# synth.net
KiCad netlist of a schematic drawn in Altium Designer
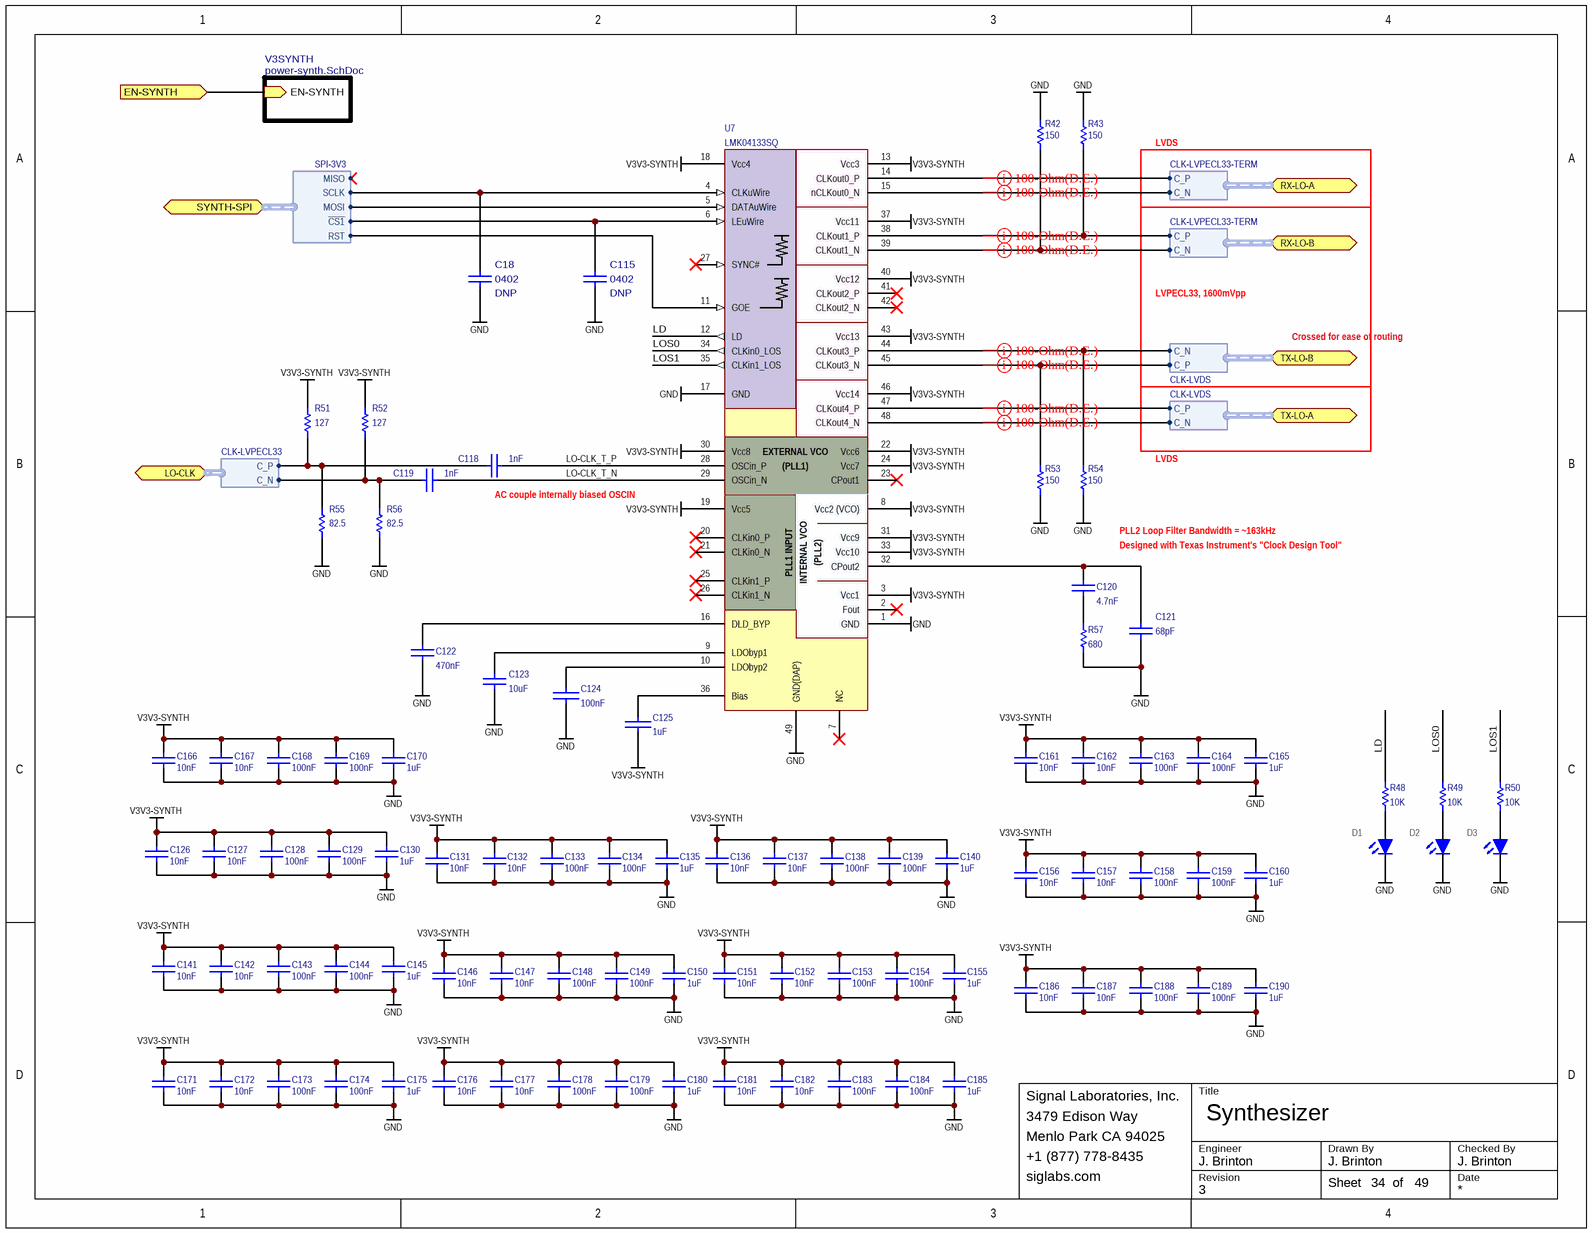
[diagram p0: synth.SchDoc]

(export (version "E")
  (design (tool "Eeschema 10.0.6"))
  (components
    (comp (ref "C18")
      (value "VJ0402A101KXA")
      (footprint "CAPC100X50X55L25N")
      (description "Ceramic Capacitor 100pF ±10% 50V C0G 0402")
      (fields
        (field (name "MANUFACTURER") "Vishay")
        (field (name "TOLERANCE") "±10%")
        (field (name "PACKAGE") "0402")
        (field (name "DO NOT PLACE") "DNP")
      )
      (libsource (lib "capacitors") (part "CAP"))
    )
    (comp (ref "C115")
      (value "VJ0402A101KXA")
      (footprint "CAPC100X50X55L25N")
      (description "Ceramic Capacitor 100pF ±10% 50V C0G 0402")
      (fields
        (field (name "MANUFACTURER") "Vishay")
        (field (name "TOLERANCE") "±10%")
        (field (name "PACKAGE") "0402")
        (field (name "DO NOT PLACE") "DNP")
      )
      (libsource (lib "capacitors") (part "CAP"))
    )
    (comp (ref "C118")
      (value "1nF")
      (footprint "CAPC100X50X55L25N")
      (description "Ceramic Capacitor 1nF ±5% 50V NP0 0402")
      (fields (field (name "VOLTAGE") "50V") (field (name "MANUFACTURER") "TDK"))
      (libsource (lib "Graviton") (part "CAP 0402"))
    )
    (comp (ref "C119")
      (value "1nF")
      (footprint "CAPC100X50X55L25N")
      (description "Ceramic Capacitor 1nF ±5% 50V NP0 0402")
      (fields (field (name "VOLTAGE") "50V") (field (name "MANUFACTURER") "TDK"))
      (libsource (lib "Graviton") (part "CAP 0402"))
    )
    (comp (ref "C120")
      (value "4.7nF")
      (footprint "CAPC100X50X55L25N")
      (description "Ceramic Capacitor 4.7nF ±5% 50V X7R 0402")
      (fields (field (name "VOLTAGE") "50V") (field (name "MANUFACTURER") "Murata"))
      (libsource (lib "Graviton") (part "CAP 0402"))
    )
    (comp (ref "C121")
      (value "68pF")
      (footprint "CAPC100X50X55L25N")
      (description "Ceramic Capacitor 68pF ±2% 50V NP0 0402")
      (fields (field (name "VOLTAGE") "50V") (field (name "MANUFACTURER") "Murata"))
      (libsource (lib "Graviton") (part "CAP 0402"))
    )
    (comp (ref "C122")
      (value "470nF")
      (footprint "CAPC200X125X145L45N")
      (description "Ceramic Capacitor 470nF ±10% 50V X7R 0805")
      (fields (field (name "VOLTAGE") "50V") (field (name "MANUFACTURER") "Kemet"))
      (libsource (lib "Graviton") (part "CAP 0402"))
    )
    (comp (ref "C123")
      (value "10uF")
      (footprint "CAPC160X80X90L20N")
      (description "Ceramic Capacitor 10uF ±20% 25V X5R 0603")
      (fields (field (name "VOLTAGE") "25V") (field (name "MANUFACTURER") "Murata"))
      (libsource (lib "Graviton") (part "CAP 0402"))
    )
    (comp (ref "C124")
      (value "100nF")
      (footprint "CAPC100X50X55L25N")
      (description "Ceramic Capacitor 100nF ±10% 16V X7R 0402")
      (fields (field (name "MANUFACTURER") "Murata") (field (name "VOLTAGE") "16V"))
      (libsource (lib "*") (part "CAP"))
    )
    (comp (ref "C125")
      (value "1uF")
      (footprint "CAPC100X50X55L25N")
      (description "Ceramic Capacitor 1uF ±10% 10V X5R 0402")
      (fields (field (name "MANUFACTURER") "Murata") (field (name "TOLERANCE") "±10%"))
      (libsource (lib "*") (part "CAP"))
    )
    (comp (ref "C126")
      (value "10nF")
      (footprint "CAPC100X50X55L25N")
      (description "Ceramic Capacitor 10nF ±10% 50V X7R 0402")
      (fields (field (name "VOLTAGE") "50V") (field (name "MANUFACTURER") "Murata"))
      (libsource (lib "Graviton") (part "CAP 0402"))
    )
    (comp (ref "C127")
      (value "10nF")
      (footprint "CAPC100X50X55L25N")
      (description "Ceramic Capacitor 10nF ±10% 50V X7R 0402")
      (fields (field (name "VOLTAGE") "50V") (field (name "MANUFACTURER") "Murata"))
      (libsource (lib "Graviton") (part "CAP 0402"))
    )
    (comp (ref "C128")
      (value "100nF")
      (footprint "CAPC100X50X55L25N")
      (description "Ceramic Capacitor 100nF ±10% 16V X7R 0402")
      (fields (field (name "VOLTAGE") "16V") (field (name "MANUFACTURER") "Murata"))
      (libsource (lib "Graviton") (part "CAP 0402"))
    )
    (comp (ref "C129")
      (value "100nF")
      (footprint "CAPC100X50X55L25N")
      (description "Ceramic Capacitor 100nF ±10% 16V X7R 0402")
      (fields (field (name "VOLTAGE") "16V") (field (name "MANUFACTURER") "Murata"))
      (libsource (lib "Graviton") (part "CAP 0402"))
    )
    (comp (ref "C130")
      (value "1uF")
      (footprint "CAPC100X50X55L25N")
      (description "Ceramic Capacitor 1uF ±10% 10V X5R 0402")
      (fields (field (name "VOLTAGE") "10V") (field (name "MANUFACTURER") "Murata"))
      (libsource (lib "Graviton") (part "CAP 0402"))
    )
    (comp (ref "C131")
      (value "10nF")
      (footprint "CAPC100X50X55L25N")
      (description "Ceramic Capacitor 10nF ±10% 50V X7R 0402")
      (fields (field (name "VOLTAGE") "50V") (field (name "MANUFACTURER") "Murata"))
      (libsource (lib "Graviton") (part "CAP 0402"))
    )
    (comp (ref "C132")
      (value "10nF")
      (footprint "CAPC100X50X55L25N")
      (description "Ceramic Capacitor 10nF ±10% 50V X7R 0402")
      (fields (field (name "VOLTAGE") "50V") (field (name "MANUFACTURER") "Murata"))
      (libsource (lib "Graviton") (part "CAP 0402"))
    )
    (comp (ref "C133")
      (value "100nF")
      (footprint "CAPC100X50X55L25N")
      (description "Ceramic Capacitor 100nF ±10% 16V X7R 0402")
      (fields (field (name "VOLTAGE") "16V") (field (name "MANUFACTURER") "Murata"))
      (libsource (lib "Graviton") (part "CAP 0402"))
    )
    (comp (ref "C134")
      (value "100nF")
      (footprint "CAPC100X50X55L25N")
      (description "Ceramic Capacitor 100nF ±10% 16V X7R 0402")
      (fields (field (name "VOLTAGE") "16V") (field (name "MANUFACTURER") "Murata"))
      (libsource (lib "Graviton") (part "CAP 0402"))
    )
    (comp (ref "C135")
      (value "1uF")
      (footprint "CAPC100X50X55L25N")
      (description "Ceramic Capacitor 1uF ±10% 10V X5R 0402")
      (fields (field (name "VOLTAGE") "10V") (field (name "MANUFACTURER") "Murata"))
      (libsource (lib "Graviton") (part "CAP 0402"))
    )
    (comp (ref "C136")
      (value "10nF")
      (footprint "CAPC100X50X55L25N")
      (description "Ceramic Capacitor 10nF ±10% 50V X7R 0402")
      (fields (field (name "VOLTAGE") "50V") (field (name "MANUFACTURER") "Murata"))
      (libsource (lib "Graviton") (part "CAP 0402"))
    )
    (comp (ref "C137")
      (value "10nF")
      (footprint "CAPC100X50X55L25N")
      (description "Ceramic Capacitor 10nF ±10% 50V X7R 0402")
      (fields (field (name "VOLTAGE") "50V") (field (name "MANUFACTURER") "Murata"))
      (libsource (lib "Graviton") (part "CAP 0402"))
    )
    (comp (ref "C138")
      (value "100nF")
      (footprint "CAPC100X50X55L25N")
      (description "Ceramic Capacitor 100nF ±10% 16V X7R 0402")
      (fields (field (name "VOLTAGE") "16V") (field (name "MANUFACTURER") "Murata"))
      (libsource (lib "Graviton") (part "CAP 0402"))
    )
    (comp (ref "C139")
      (value "100nF")
      (footprint "CAPC100X50X55L25N")
      (description "Ceramic Capacitor 100nF ±10% 16V X7R 0402")
      (fields (field (name "VOLTAGE") "16V") (field (name "MANUFACTURER") "Murata"))
      (libsource (lib "Graviton") (part "CAP 0402"))
    )
    (comp (ref "C140")
      (value "1uF")
      (footprint "CAPC100X50X55L25N")
      (description "Ceramic Capacitor 1uF ±10% 10V X5R 0402")
      (fields (field (name "VOLTAGE") "10V") (field (name "MANUFACTURER") "Murata"))
      (libsource (lib "Graviton") (part "CAP 0402"))
    )
    (comp (ref "C141")
      (value "10nF")
      (footprint "CAPC100X50X55L25N")
      (description "Ceramic Capacitor 10nF ±10% 50V X7R 0402")
      (fields (field (name "VOLTAGE") "50V") (field (name "MANUFACTURER") "Murata"))
      (libsource (lib "Graviton") (part "CAP 0402"))
    )
    (comp (ref "C142")
      (value "10nF")
      (footprint "CAPC100X50X55L25N")
      (description "Ceramic Capacitor 10nF ±10% 50V X7R 0402")
      (fields (field (name "VOLTAGE") "50V") (field (name "MANUFACTURER") "Murata"))
      (libsource (lib "Graviton") (part "CAP 0402"))
    )
    (comp (ref "C143")
      (value "100nF")
      (footprint "CAPC100X50X55L25N")
      (description "Ceramic Capacitor 100nF ±10% 16V X7R 0402")
      (fields (field (name "VOLTAGE") "16V") (field (name "MANUFACTURER") "Murata"))
      (libsource (lib "Graviton") (part "CAP 0402"))
    )
    (comp (ref "C144")
      (value "100nF")
      (footprint "CAPC100X50X55L25N")
      (description "Ceramic Capacitor 100nF ±10% 16V X7R 0402")
      (fields (field (name "VOLTAGE") "16V") (field (name "MANUFACTURER") "Murata"))
      (libsource (lib "Graviton") (part "CAP 0402"))
    )
    (comp (ref "C145")
      (value "1uF")
      (footprint "CAPC100X50X55L25N")
      (description "Ceramic Capacitor 1uF ±10% 10V X5R 0402")
      (fields (field (name "VOLTAGE") "10V") (field (name "MANUFACTURER") "Murata"))
      (libsource (lib "Graviton") (part "CAP 0402"))
    )
    (comp (ref "C146")
      (value "10nF")
      (footprint "CAPC100X50X55L25N")
      (description "Ceramic Capacitor 10nF ±10% 50V X7R 0402")
      (fields (field (name "VOLTAGE") "50V") (field (name "MANUFACTURER") "Murata"))
      (libsource (lib "Graviton") (part "CAP 0402"))
    )
    (comp (ref "C147")
      (value "10nF")
      (footprint "CAPC100X50X55L25N")
      (description "Ceramic Capacitor 10nF ±10% 50V X7R 0402")
      (fields (field (name "VOLTAGE") "50V") (field (name "MANUFACTURER") "Murata"))
      (libsource (lib "Graviton") (part "CAP 0402"))
    )
    (comp (ref "C148")
      (value "100nF")
      (footprint "CAPC100X50X55L25N")
      (description "Ceramic Capacitor 100nF ±10% 16V X7R 0402")
      (fields (field (name "VOLTAGE") "16V") (field (name "MANUFACTURER") "Murata"))
      (libsource (lib "Graviton") (part "CAP 0402"))
    )
    (comp (ref "C149")
      (value "100nF")
      (footprint "CAPC100X50X55L25N")
      (description "Ceramic Capacitor 100nF ±10% 16V X7R 0402")
      (fields (field (name "VOLTAGE") "16V") (field (name "MANUFACTURER") "Murata"))
      (libsource (lib "Graviton") (part "CAP 0402"))
    )
    (comp (ref "C150")
      (value "1uF")
      (footprint "CAPC100X50X55L25N")
      (description "Ceramic Capacitor 1uF ±10% 10V X5R 0402")
      (fields (field (name "VOLTAGE") "10V") (field (name "MANUFACTURER") "Murata"))
      (libsource (lib "Graviton") (part "CAP 0402"))
    )
    (comp (ref "C151")
      (value "10nF")
      (footprint "CAPC100X50X55L25N")
      (description "Ceramic Capacitor 10nF ±10% 50V X7R 0402")
      (fields (field (name "VOLTAGE") "50V") (field (name "MANUFACTURER") "Murata"))
      (libsource (lib "Graviton") (part "CAP 0402"))
    )
    (comp (ref "C152")
      (value "10nF")
      (footprint "CAPC100X50X55L25N")
      (description "Ceramic Capacitor 10nF ±10% 50V X7R 0402")
      (fields (field (name "VOLTAGE") "50V") (field (name "MANUFACTURER") "Murata"))
      (libsource (lib "Graviton") (part "CAP 0402"))
    )
    (comp (ref "C153")
      (value "100nF")
      (footprint "CAPC100X50X55L25N")
      (description "Ceramic Capacitor 100nF ±10% 16V X7R 0402")
      (fields (field (name "VOLTAGE") "16V") (field (name "MANUFACTURER") "Murata"))
      (libsource (lib "Graviton") (part "CAP 0402"))
    )
    (comp (ref "C154")
      (value "100nF")
      (footprint "CAPC100X50X55L25N")
      (description "Ceramic Capacitor 100nF ±10% 16V X7R 0402")
      (fields (field (name "VOLTAGE") "16V") (field (name "MANUFACTURER") "Murata"))
      (libsource (lib "Graviton") (part "CAP 0402"))
    )
    (comp (ref "C155")
      (value "1uF")
      (footprint "CAPC100X50X55L25N")
      (description "Ceramic Capacitor 1uF ±10% 10V X5R 0402")
      (fields (field (name "VOLTAGE") "10V") (field (name "MANUFACTURER") "Murata"))
      (libsource (lib "Graviton") (part "CAP 0402"))
    )
    (comp (ref "C156")
      (value "10nF")
      (footprint "CAPC100X50X55L25N")
      (description "Ceramic Capacitor 10nF ±10% 50V X7R 0402")
      (fields (field (name "VOLTAGE") "50V") (field (name "MANUFACTURER") "Murata"))
      (libsource (lib "Graviton") (part "CAP 0402"))
    )
    (comp (ref "C157")
      (value "10nF")
      (footprint "CAPC100X50X55L25N")
      (description "Ceramic Capacitor 10nF ±10% 50V X7R 0402")
      (fields (field (name "VOLTAGE") "50V") (field (name "MANUFACTURER") "Murata"))
      (libsource (lib "Graviton") (part "CAP 0402"))
    )
    (comp (ref "C158")
      (value "100nF")
      (footprint "CAPC100X50X55L25N")
      (description "Ceramic Capacitor 100nF ±10% 16V X7R 0402")
      (fields (field (name "VOLTAGE") "16V") (field (name "MANUFACTURER") "Murata"))
      (libsource (lib "Graviton") (part "CAP 0402"))
    )
    (comp (ref "C159")
      (value "100nF")
      (footprint "CAPC100X50X55L25N")
      (description "Ceramic Capacitor 100nF ±10% 16V X7R 0402")
      (fields (field (name "VOLTAGE") "16V") (field (name "MANUFACTURER") "Murata"))
      (libsource (lib "Graviton") (part "CAP 0402"))
    )
    (comp (ref "C160")
      (value "1uF")
      (footprint "CAPC100X50X55L25N")
      (description "Ceramic Capacitor 1uF ±10% 10V X5R 0402")
      (fields (field (name "VOLTAGE") "10V") (field (name "MANUFACTURER") "Murata"))
      (libsource (lib "Graviton") (part "CAP 0402"))
    )
    (comp (ref "C161")
      (value "10nF")
      (footprint "CAPC100X50X55L25N")
      (description "Ceramic Capacitor 10nF ±10% 50V X7R 0402")
      (fields (field (name "VOLTAGE") "50V") (field (name "MANUFACTURER") "Murata"))
      (libsource (lib "Graviton") (part "CAP 0402"))
    )
    (comp (ref "C162")
      (value "10nF")
      (footprint "CAPC100X50X55L25N")
      (description "Ceramic Capacitor 10nF ±10% 50V X7R 0402")
      (fields (field (name "VOLTAGE") "50V") (field (name "MANUFACTURER") "Murata"))
      (libsource (lib "Graviton") (part "CAP 0402"))
    )
    (comp (ref "C163")
      (value "100nF")
      (footprint "CAPC100X50X55L25N")
      (description "Ceramic Capacitor 100nF ±10% 16V X7R 0402")
      (fields (field (name "VOLTAGE") "16V") (field (name "MANUFACTURER") "Murata"))
      (libsource (lib "Graviton") (part "CAP 0402"))
    )
    (comp (ref "C164")
      (value "100nF")
      (footprint "CAPC100X50X55L25N")
      (description "Ceramic Capacitor 100nF ±10% 16V X7R 0402")
      (fields (field (name "VOLTAGE") "16V") (field (name "MANUFACTURER") "Murata"))
      (libsource (lib "Graviton") (part "CAP 0402"))
    )
    (comp (ref "C165")
      (value "1uF")
      (footprint "CAPC100X50X55L25N")
      (description "Ceramic Capacitor 1uF ±10% 10V X5R 0402")
      (fields (field (name "VOLTAGE") "10V") (field (name "MANUFACTURER") "Murata"))
      (libsource (lib "Graviton") (part "CAP 0402"))
    )
    (comp (ref "C166")
      (value "10nF")
      (footprint "CAPC100X50X55L25N")
      (description "Ceramic Capacitor 10nF ±10% 50V X7R 0402")
      (fields (field (name "VOLTAGE") "50V") (field (name "MANUFACTURER") "Murata"))
      (libsource (lib "Graviton") (part "CAP 0402"))
    )
    (comp (ref "C167")
      (value "10nF")
      (footprint "CAPC100X50X55L25N")
      (description "Ceramic Capacitor 10nF ±10% 50V X7R 0402")
      (fields (field (name "VOLTAGE") "50V") (field (name "MANUFACTURER") "Murata"))
      (libsource (lib "Graviton") (part "CAP 0402"))
    )
    (comp (ref "C168")
      (value "100nF")
      (footprint "CAPC100X50X55L25N")
      (description "Ceramic Capacitor 100nF ±10% 16V X7R 0402")
      (fields (field (name "VOLTAGE") "16V") (field (name "MANUFACTURER") "Murata"))
      (libsource (lib "Graviton") (part "CAP 0402"))
    )
    (comp (ref "C169")
      (value "100nF")
      (footprint "CAPC100X50X55L25N")
      (description "Ceramic Capacitor 100nF ±10% 16V X7R 0402")
      (fields (field (name "VOLTAGE") "16V") (field (name "MANUFACTURER") "Murata"))
      (libsource (lib "Graviton") (part "CAP 0402"))
    )
    (comp (ref "C170")
      (value "1uF")
      (footprint "CAPC100X50X55L25N")
      (description "Ceramic Capacitor 1uF ±10% 10V X5R 0402")
      (fields (field (name "VOLTAGE") "10V") (field (name "MANUFACTURER") "Murata"))
      (libsource (lib "Graviton") (part "CAP 0402"))
    )
    (comp (ref "C171")
      (value "10nF")
      (footprint "CAPC100X50X55L25N")
      (description "Ceramic Capacitor 10nF ±10% 50V X7R 0402")
      (fields (field (name "VOLTAGE") "50V") (field (name "MANUFACTURER") "Murata"))
      (libsource (lib "Graviton") (part "CAP 0402"))
    )
    (comp (ref "C172")
      (value "10nF")
      (footprint "CAPC100X50X55L25N")
      (description "Ceramic Capacitor 10nF ±10% 50V X7R 0402")
      (fields (field (name "VOLTAGE") "50V") (field (name "MANUFACTURER") "Murata"))
      (libsource (lib "Graviton") (part "CAP 0402"))
    )
    (comp (ref "C173")
      (value "100nF")
      (footprint "CAPC100X50X55L25N")
      (description "Ceramic Capacitor 100nF ±10% 16V X7R 0402")
      (fields (field (name "VOLTAGE") "16V") (field (name "MANUFACTURER") "Murata"))
      (libsource (lib "Graviton") (part "CAP 0402"))
    )
    (comp (ref "C174")
      (value "100nF")
      (footprint "CAPC100X50X55L25N")
      (description "Ceramic Capacitor 100nF ±10% 16V X7R 0402")
      (fields (field (name "VOLTAGE") "16V") (field (name "MANUFACTURER") "Murata"))
      (libsource (lib "Graviton") (part "CAP 0402"))
    )
    (comp (ref "C175")
      (value "1uF")
      (footprint "CAPC100X50X55L25N")
      (description "Ceramic Capacitor 1uF ±10% 10V X5R 0402")
      (fields (field (name "VOLTAGE") "10V") (field (name "MANUFACTURER") "Murata"))
      (libsource (lib "Graviton") (part "CAP 0402"))
    )
    (comp (ref "C176")
      (value "10nF")
      (footprint "CAPC100X50X55L25N")
      (description "Ceramic Capacitor 10nF ±10% 50V X7R 0402")
      (fields (field (name "VOLTAGE") "50V") (field (name "MANUFACTURER") "Murata"))
      (libsource (lib "Graviton") (part "CAP 0402"))
    )
    (comp (ref "C177")
      (value "10nF")
      (footprint "CAPC100X50X55L25N")
      (description "Ceramic Capacitor 10nF ±10% 50V X7R 0402")
      (fields (field (name "VOLTAGE") "50V") (field (name "MANUFACTURER") "Murata"))
      (libsource (lib "Graviton") (part "CAP 0402"))
    )
    (comp (ref "C178")
      (value "100nF")
      (footprint "CAPC100X50X55L25N")
      (description "Ceramic Capacitor 100nF ±10% 16V X7R 0402")
      (fields (field (name "VOLTAGE") "16V") (field (name "MANUFACTURER") "Murata"))
      (libsource (lib "Graviton") (part "CAP 0402"))
    )
    (comp (ref "C179")
      (value "100nF")
      (footprint "CAPC100X50X55L25N")
      (description "Ceramic Capacitor 100nF ±10% 16V X7R 0402")
      (fields (field (name "VOLTAGE") "16V") (field (name "MANUFACTURER") "Murata"))
      (libsource (lib "Graviton") (part "CAP 0402"))
    )
    (comp (ref "C180")
      (value "1uF")
      (footprint "CAPC100X50X55L25N")
      (description "Ceramic Capacitor 1uF ±10% 10V X5R 0402")
      (fields (field (name "VOLTAGE") "10V") (field (name "MANUFACTURER") "Murata"))
      (libsource (lib "Graviton") (part "CAP 0402"))
    )
    (comp (ref "C181")
      (value "10nF")
      (footprint "CAPC100X50X55L25N")
      (description "Ceramic Capacitor 10nF ±10% 50V X7R 0402")
      (fields (field (name "VOLTAGE") "50V") (field (name "MANUFACTURER") "Murata"))
      (libsource (lib "Graviton") (part "CAP 0402"))
    )
    (comp (ref "C182")
      (value "10nF")
      (footprint "CAPC100X50X55L25N")
      (description "Ceramic Capacitor 10nF ±10% 50V X7R 0402")
      (fields (field (name "VOLTAGE") "50V") (field (name "MANUFACTURER") "Murata"))
      (libsource (lib "Graviton") (part "CAP 0402"))
    )
    (comp (ref "C183")
      (value "100nF")
      (footprint "CAPC100X50X55L25N")
      (description "Ceramic Capacitor 100nF ±10% 16V X7R 0402")
      (fields (field (name "VOLTAGE") "16V") (field (name "MANUFACTURER") "Murata"))
      (libsource (lib "Graviton") (part "CAP 0402"))
    )
    (comp (ref "C184")
      (value "100nF")
      (footprint "CAPC100X50X55L25N")
      (description "Ceramic Capacitor 100nF ±10% 16V X7R 0402")
      (fields (field (name "VOLTAGE") "16V") (field (name "MANUFACTURER") "Murata"))
      (libsource (lib "Graviton") (part "CAP 0402"))
    )
    (comp (ref "C185")
      (value "1uF")
      (footprint "CAPC100X50X55L25N")
      (description "Ceramic Capacitor 1uF ±10% 10V X5R 0402")
      (fields (field (name "VOLTAGE") "10V") (field (name "MANUFACTURER") "Murata"))
      (libsource (lib "Graviton") (part "CAP 0402"))
    )
    (comp (ref "C186")
      (value "10nF")
      (footprint "CAPC100X50X55L25N")
      (description "Ceramic Capacitor 10nF ±10% 50V X7R 0402")
      (fields (field (name "VOLTAGE") "50V") (field (name "MANUFACTURER") "Murata"))
      (libsource (lib "Graviton") (part "CAP 0402"))
    )
    (comp (ref "C187")
      (value "10nF")
      (footprint "CAPC100X50X55L25N")
      (description "Ceramic Capacitor 10nF ±10% 50V X7R 0402")
      (fields (field (name "VOLTAGE") "50V") (field (name "MANUFACTURER") "Murata"))
      (libsource (lib "Graviton") (part "CAP 0402"))
    )
    (comp (ref "C188")
      (value "100nF")
      (footprint "CAPC100X50X55L25N")
      (description "Ceramic Capacitor 100nF ±10% 16V X7R 0402")
      (fields (field (name "VOLTAGE") "16V") (field (name "MANUFACTURER") "Murata"))
      (libsource (lib "Graviton") (part "CAP 0402"))
    )
    (comp (ref "C189")
      (value "100nF")
      (footprint "CAPC100X50X55L25N")
      (description "Ceramic Capacitor 100nF ±10% 16V X7R 0402")
      (fields (field (name "VOLTAGE") "16V") (field (name "MANUFACTURER") "Murata"))
      (libsource (lib "Graviton") (part "CAP 0402"))
    )
    (comp (ref "C190")
      (value "1uF")
      (footprint "CAPC100X50X55L25N")
      (description "Ceramic Capacitor 1uF ±10% 10V X5R 0402")
      (fields (field (name "VOLTAGE") "10V") (field (name "MANUFACTURER") "Murata"))
      (libsource (lib "Graviton") (part "CAP 0402"))
    )
    (comp (ref "D1")
      (value "LNJ237W82RA")
      (footprint "0603_LED")
      (description "LED, SMT 0603, Color Red, 10mA, 2.05V")
      (fields (field (name "MANUFACTURER") "Panasonic"))
      (libsource (lib "generic") (part "LED0603Y"))
    )
    (comp (ref "D2")
      (value "LNJ237W82RA")
      (footprint "0603_LED")
      (description "LED, SMT 0603, Color Red, 10mA, 2.05V")
      (fields (field (name "MANUFACTURER") "Panasonic"))
      (libsource (lib "generic") (part "LED0603Y"))
    )
    (comp (ref "D3")
      (value "LNJ237W82RA")
      (footprint "0603_LED")
      (description "LED, SMT 0603, Color Red, 10mA, 2.05V")
      (fields (field (name "MANUFACTURER") "Panasonic"))
      (libsource (lib "generic") (part "LED0603Y"))
    )
    (comp (ref "R42")
      (value "150")
      (footprint "RESC1005X40N")
      (description "Thick Film 150 ±1% 0402")
      (fields (field (name "MANUFACTURER") "Panasonic") (field (name "TOLERANCE") "±1%"))
      (libsource (lib "Graviton") (part "RES 0402"))
    )
    (comp (ref "R43")
      (value "150")
      (footprint "RESC1005X40N")
      (description "Thick Film 150 ±1% 0402")
      (fields (field (name "MANUFACTURER") "Panasonic") (field (name "TOLERANCE") "±1%"))
      (libsource (lib "Graviton") (part "RES 0402"))
    )
    (comp (ref "R48")
      (value "10K")
      (footprint "RESC1005X40N")
      (description "Thick Film Resistor 10k ±1% 0.1W 50V 0402")
      (fields (field (name "MANUFACTURER") "Panasonic") (field (name "TOLERANCE") "±1%"))
      (libsource (lib "Graviton") (part "RES 0402"))
    )
    (comp (ref "R49")
      (value "10K")
      (footprint "RESC1005X40N")
      (description "Thick Film Resistor 10k ±1% 0.1W 50V 0402")
      (fields (field (name "MANUFACTURER") "Panasonic") (field (name "TOLERANCE") "±1%"))
      (libsource (lib "Graviton") (part "RES 0402"))
    )
    (comp (ref "R50")
      (value "10K")
      (footprint "RESC1005X40N")
      (description "Thick Film Resistor 10k ±1% 0.1W 50V 0402")
      (fields (field (name "MANUFACTURER") "Panasonic") (field (name "TOLERANCE") "±1%"))
      (libsource (lib "Graviton") (part "RES 0402"))
    )
    (comp (ref "R51")
      (value "127")
      (footprint "RESC1005X40N")
      (description "Thin Film Resistor 127 ±0.1% 0402")
      (fields (field (name "MANUFACTURER") "Panasonic") (field (name "TOLERANCE") "±0.1%"))
      (libsource (lib "Graviton") (part "RES 0402"))
    )
    (comp (ref "R52")
      (value "127")
      (footprint "RESC1005X40N")
      (description "Thin Film Resistor 127 ±0.1% 0402")
      (fields (field (name "MANUFACTURER") "Panasonic") (field (name "TOLERANCE") "±0.1%"))
      (libsource (lib "Graviton") (part "RES 0402"))
    )
    (comp (ref "R53")
      (value "150")
      (footprint "RESC1005X40N")
      (description "Thick Film 150 ±1% 0402")
      (fields (field (name "MANUFACTURER") "Panasonic") (field (name "TOLERANCE") "±1%"))
      (libsource (lib "Graviton") (part "RES 0402"))
    )
    (comp (ref "R54")
      (value "150")
      (footprint "RESC1005X40N")
      (description "Thick Film 150 ±1% 0402")
      (fields (field (name "MANUFACTURER") "Panasonic") (field (name "TOLERANCE") "±1%"))
      (libsource (lib "Graviton") (part "RES 0402"))
    )
    (comp (ref "R55")
      (value "82.5")
      (footprint "RESC1005X40N")
      (description "Thin Film Resistor 82.5 ±0.1% 0402")
      (fields (field (name "MANUFACTURER") "Panasonic") (field (name "TOLERANCE") "±0.1%"))
      (libsource (lib "Graviton") (part "RES 0402"))
    )
    (comp (ref "R56")
      (value "82.5")
      (footprint "RESC1005X40N")
      (description "Thin Film Resistor 82.5 ±0.1% 0402")
      (fields (field (name "MANUFACTURER") "Panasonic") (field (name "TOLERANCE") "±0.1%"))
      (libsource (lib "Graviton") (part "RES 0402"))
    )
    (comp (ref "R57")
      (value "680")
      (footprint "RESC1005X40N")
      (description "Thick Film Resistor 680 ±1% 0402")
      (fields (field (name "MANUFACTURER") "Yageo") (field (name "TOLERANCE") "±1%"))
      (libsource (lib "Graviton") (part "RES 0402"))
    )
    (comp (ref "U7")
      (value "LMK04133SQ")
      (footprint "texas_instruments:RHS")
      (description "Clock Jitter Cleaner with Cascaded PLLs")
      (fields (field (name "MANUFACTURER") "Texas Instruments"))
      (libsource (lib "ti") (part "LMK04133"))
    )
  )
  (nets
    (net (code "6") (name "/LD") (class "Default")
      (node (ref "R48") (pin "2") (pinfunction "2_2") (pintype "passive"))
      (node (ref "U7") (pin "12") (pinfunction "LD_12") (pintype "output"))
    )
    (net (code "7") (name "/LO-CLK_T_N") (class "Default")
      (node (ref "C119") (pin "1") (pinfunction "1_1") (pintype "passive"))
      (node (ref "U7") (pin "29") (pinfunction "OSCin_N_29") (pintype "passive"))
    )
    (net (code "8") (name "/LO-CLK_T_P") (class "Default")
      (node (ref "C118") (pin "1") (pinfunction "1_1") (pintype "passive"))
      (node (ref "U7") (pin "28") (pinfunction "OSCin_P_28") (pintype "passive"))
    )
    (net (code "9") (name "/LOS0") (class "Default")
      (node (ref "R49") (pin "2") (pinfunction "2_2") (pintype "passive"))
      (node (ref "U7") (pin "34") (pinfunction "CLKin0_LOS_34") (pintype "output"))
    )
    (net (code "10") (name "/LOS1") (class "Default")
      (node (ref "R50") (pin "2") (pinfunction "2_2") (pintype "passive"))
      (node (ref "U7") (pin "35") (pinfunction "CLKin1_LOS_35") (pintype "output"))
    )
    (net (code "11") (name "/MOSI") (class "Default")
      (node (ref "U7") (pin "5") (pinfunction "DATAuWire_5") (pintype "input"))
    )
    (net (code "12") (name "/RST") (class "Default")
      (node (ref "U7") (pin "11") (pinfunction "GOE_11") (pintype "input"))
    )
    (net (code "13") (name "/SCLK") (class "Default")
      (node (ref "C18") (pin "1") (pinfunction "1_1") (pintype "passive"))
      (node (ref "U7") (pin "4") (pinfunction "CLKuWire_4") (pintype "input"))
    )
    (net (code "18") (name "/~{CS1}") (class "Default")
      (node (ref "C115") (pin "1") (pinfunction "1_1") (pintype "passive"))
      (node (ref "U7") (pin "6") (pinfunction "LEuWire_6") (pintype "input"))
    )
    (net (code "19") (name "GND") (class "Default")
      (node (ref "C115") (pin "2") (pinfunction "2_2") (pintype "passive"))
      (node (ref "C121") (pin "1") (pinfunction "1_1") (pintype "passive"))
      (node (ref "C122") (pin "1") (pinfunction "1_1") (pintype "passive"))
      (node (ref "C123") (pin "1") (pinfunction "1_1") (pintype "passive"))
      (node (ref "C124") (pin "1") (pinfunction "1_1") (pintype "passive"))
      (node (ref "C126") (pin "1") (pinfunction "1_1") (pintype "passive"))
      (node (ref "C127") (pin "1") (pinfunction "1_1") (pintype "passive"))
      (node (ref "C128") (pin "1") (pinfunction "1_1") (pintype "passive"))
      (node (ref "C129") (pin "1") (pinfunction "1_1") (pintype "passive"))
      (node (ref "C130") (pin "1") (pinfunction "1_1") (pintype "passive"))
      (node (ref "C131") (pin "1") (pinfunction "1_1") (pintype "passive"))
      (node (ref "C132") (pin "1") (pinfunction "1_1") (pintype "passive"))
      (node (ref "C133") (pin "1") (pinfunction "1_1") (pintype "passive"))
      (node (ref "C134") (pin "1") (pinfunction "1_1") (pintype "passive"))
      (node (ref "C135") (pin "1") (pinfunction "1_1") (pintype "passive"))
      (node (ref "C136") (pin "1") (pinfunction "1_1") (pintype "passive"))
      (node (ref "C137") (pin "1") (pinfunction "1_1") (pintype "passive"))
      (node (ref "C138") (pin "1") (pinfunction "1_1") (pintype "passive"))
      (node (ref "C139") (pin "1") (pinfunction "1_1") (pintype "passive"))
      (node (ref "C140") (pin "1") (pinfunction "1_1") (pintype "passive"))
      (node (ref "C141") (pin "1") (pinfunction "1_1") (pintype "passive"))
      (node (ref "C142") (pin "1") (pinfunction "1_1") (pintype "passive"))
      (node (ref "C143") (pin "1") (pinfunction "1_1") (pintype "passive"))
      (node (ref "C144") (pin "1") (pinfunction "1_1") (pintype "passive"))
      (node (ref "C145") (pin "1") (pinfunction "1_1") (pintype "passive"))
      (node (ref "C146") (pin "1") (pinfunction "1_1") (pintype "passive"))
      (node (ref "C147") (pin "1") (pinfunction "1_1") (pintype "passive"))
      (node (ref "C148") (pin "1") (pinfunction "1_1") (pintype "passive"))
      (node (ref "C149") (pin "1") (pinfunction "1_1") (pintype "passive"))
      (node (ref "C150") (pin "1") (pinfunction "1_1") (pintype "passive"))
      (node (ref "C151") (pin "1") (pinfunction "1_1") (pintype "passive"))
      (node (ref "C152") (pin "1") (pinfunction "1_1") (pintype "passive"))
      (node (ref "C153") (pin "1") (pinfunction "1_1") (pintype "passive"))
      (node (ref "C154") (pin "1") (pinfunction "1_1") (pintype "passive"))
      (node (ref "C155") (pin "1") (pinfunction "1_1") (pintype "passive"))
      (node (ref "C156") (pin "1") (pinfunction "1_1") (pintype "passive"))
      (node (ref "C157") (pin "1") (pinfunction "1_1") (pintype "passive"))
      (node (ref "C158") (pin "1") (pinfunction "1_1") (pintype "passive"))
      (node (ref "C159") (pin "1") (pinfunction "1_1") (pintype "passive"))
      (node (ref "C160") (pin "1") (pinfunction "1_1") (pintype "passive"))
      (node (ref "C161") (pin "1") (pinfunction "1_1") (pintype "passive"))
      (node (ref "C162") (pin "1") (pinfunction "1_1") (pintype "passive"))
      (node (ref "C163") (pin "1") (pinfunction "1_1") (pintype "passive"))
      (node (ref "C164") (pin "1") (pinfunction "1_1") (pintype "passive"))
      (node (ref "C165") (pin "1") (pinfunction "1_1") (pintype "passive"))
      (node (ref "C166") (pin "1") (pinfunction "1_1") (pintype "passive"))
      (node (ref "C167") (pin "1") (pinfunction "1_1") (pintype "passive"))
      (node (ref "C168") (pin "1") (pinfunction "1_1") (pintype "passive"))
      (node (ref "C169") (pin "1") (pinfunction "1_1") (pintype "passive"))
      (node (ref "C170") (pin "1") (pinfunction "1_1") (pintype "passive"))
      (node (ref "C171") (pin "1") (pinfunction "1_1") (pintype "passive"))
      (node (ref "C172") (pin "1") (pinfunction "1_1") (pintype "passive"))
      (node (ref "C173") (pin "1") (pinfunction "1_1") (pintype "passive"))
      (node (ref "C174") (pin "1") (pinfunction "1_1") (pintype "passive"))
      (node (ref "C175") (pin "1") (pinfunction "1_1") (pintype "passive"))
      (node (ref "C176") (pin "1") (pinfunction "1_1") (pintype "passive"))
      (node (ref "C177") (pin "1") (pinfunction "1_1") (pintype "passive"))
      (node (ref "C178") (pin "1") (pinfunction "1_1") (pintype "passive"))
      (node (ref "C179") (pin "1") (pinfunction "1_1") (pintype "passive"))
      (node (ref "C18") (pin "2") (pinfunction "2_2") (pintype "passive"))
      (node (ref "C180") (pin "1") (pinfunction "1_1") (pintype "passive"))
      (node (ref "C181") (pin "1") (pinfunction "1_1") (pintype "passive"))
      (node (ref "C182") (pin "1") (pinfunction "1_1") (pintype "passive"))
      (node (ref "C183") (pin "1") (pinfunction "1_1") (pintype "passive"))
      (node (ref "C184") (pin "1") (pinfunction "1_1") (pintype "passive"))
      (node (ref "C185") (pin "1") (pinfunction "1_1") (pintype "passive"))
      (node (ref "C186") (pin "1") (pinfunction "1_1") (pintype "passive"))
      (node (ref "C187") (pin "1") (pinfunction "1_1") (pintype "passive"))
      (node (ref "C188") (pin "1") (pinfunction "1_1") (pintype "passive"))
      (node (ref "C189") (pin "1") (pinfunction "1_1") (pintype "passive"))
      (node (ref "C190") (pin "1") (pinfunction "1_1") (pintype "passive"))
      (node (ref "D1") (pin "2") (pinfunction "K_2") (pintype "passive"))
      (node (ref "D2") (pin "2") (pinfunction "K_2") (pintype "passive"))
      (node (ref "D3") (pin "2") (pinfunction "K_2") (pintype "passive"))
      (node (ref "R42") (pin "2") (pinfunction "2_2") (pintype "passive"))
      (node (ref "R43") (pin "2") (pinfunction "2_2") (pintype "passive"))
      (node (ref "R53") (pin "1") (pinfunction "1_1") (pintype "passive"))
      (node (ref "R54") (pin "1") (pinfunction "1_1") (pintype "passive"))
      (node (ref "R55") (pin "1") (pinfunction "1_1") (pintype "passive"))
      (node (ref "R56") (pin "1") (pinfunction "1_1") (pintype "passive"))
      (node (ref "R57") (pin "2") (pinfunction "2_2") (pintype "passive"))
      (node (ref "U7") (pin "1") (pinfunction "GND_1") (pintype "power_in"))
      (node (ref "U7") (pin "17") (pinfunction "GND_17") (pintype "power_in"))
      (node (ref "U7") (pin "49") (pinfunction "GND(DAP)_49") (pintype "power_in"))
    )
    (net (code "20") (name "Net-(C118-Pad2)") (class "Default")
      (node (ref "C118") (pin "2") (pinfunction "2_2") (pintype "passive"))
      (node (ref "R51") (pin "1") (pinfunction "1_1") (pintype "passive"))
      (node (ref "R55") (pin "2") (pinfunction "2_2") (pintype "passive"))
    )
    (net (code "21") (name "Net-(C119-Pad2)") (class "Default")
      (node (ref "C119") (pin "2") (pinfunction "2_2") (pintype "passive"))
      (node (ref "R52") (pin "1") (pinfunction "1_1") (pintype "passive"))
      (node (ref "R56") (pin "2") (pinfunction "2_2") (pintype "passive"))
    )
    (net (code "22") (name "Net-(C120-Pad1)") (class "Default")
      (node (ref "C120") (pin "1") (pinfunction "1_1") (pintype "passive"))
      (node (ref "R57") (pin "1") (pinfunction "1_1") (pintype "passive"))
    )
    (net (code "23") (name "Net-(D1-A)") (class "Default")
      (node (ref "D1") (pin "1") (pinfunction "A_1") (pintype "passive"))
      (node (ref "R48") (pin "1") (pinfunction "1_1") (pintype "passive"))
    )
    (net (code "24") (name "Net-(D2-A)") (class "Default")
      (node (ref "D2") (pin "1") (pinfunction "A_1") (pintype "passive"))
      (node (ref "R49") (pin "1") (pinfunction "1_1") (pintype "passive"))
    )
    (net (code "25") (name "Net-(D3-A)") (class "Default")
      (node (ref "D3") (pin "1") (pinfunction "A_1") (pintype "passive"))
      (node (ref "R50") (pin "1") (pinfunction "1_1") (pintype "passive"))
    )
    (net (code "26") (name "Net-(U7-Bias)") (class "Default")
      (node (ref "C125") (pin "2") (pinfunction "2_2") (pintype "passive"))
      (node (ref "U7") (pin "36") (pinfunction "Bias_36") (pintype "passive"))
    )
    (net (code "27") (name "Net-(U7-CLKout1_N)") (class "Default")
      (node (ref "R42") (pin "1") (pinfunction "1_1") (pintype "passive"))
      (node (ref "U7") (pin "39") (pinfunction "CLKout1_N_39") (pintype "passive"))
    )
    (net (code "28") (name "Net-(U7-CLKout1_P)") (class "Default")
      (node (ref "R43") (pin "1") (pinfunction "1_1") (pintype "passive"))
      (node (ref "U7") (pin "38") (pinfunction "CLKout1_P_38") (pintype "passive"))
    )
    (net (code "29") (name "Net-(U7-CLKout3_N)") (class "Default")
      (node (ref "R53") (pin "2") (pinfunction "2_2") (pintype "passive"))
      (node (ref "U7") (pin "45") (pinfunction "CLKout3_N_45") (pintype "passive"))
    )
    (net (code "30") (name "Net-(U7-CLKout3_P)") (class "Default")
      (node (ref "R54") (pin "2") (pinfunction "2_2") (pintype "passive"))
      (node (ref "U7") (pin "44") (pinfunction "CLKout3_P_44") (pintype "passive"))
    )
    (net (code "31") (name "Net-(U7-CPout2)") (class "Default")
      (node (ref "C120") (pin "2") (pinfunction "2_2") (pintype "passive"))
      (node (ref "C121") (pin "2") (pinfunction "2_2") (pintype "passive"))
      (node (ref "U7") (pin "32") (pinfunction "CPout2_32") (pintype "passive"))
    )
    (net (code "32") (name "Net-(U7-DLD_BYP)") (class "Default")
      (node (ref "C122") (pin "2") (pinfunction "2_2") (pintype "passive"))
      (node (ref "U7") (pin "16") (pinfunction "DLD_BYP_16") (pintype "passive"))
    )
    (net (code "33") (name "Net-(U7-LDObyp1)") (class "Default")
      (node (ref "C123") (pin "2") (pinfunction "2_2") (pintype "passive"))
      (node (ref "U7") (pin "9") (pinfunction "LDObyp1_9") (pintype "passive"))
    )
    (net (code "34") (name "Net-(U7-LDObyp2)") (class "Default")
      (node (ref "C124") (pin "2") (pinfunction "2_2") (pintype "passive"))
      (node (ref "U7") (pin "10") (pinfunction "LDObyp2_10") (pintype "passive"))
    )
    (net (code "35") (name "V3V3-SYNTH") (class "Default")
      (node (ref "C125") (pin "1") (pinfunction "1_1") (pintype "passive"))
      (node (ref "C126") (pin "2") (pinfunction "2_2") (pintype "passive"))
      (node (ref "C127") (pin "2") (pinfunction "2_2") (pintype "passive"))
      (node (ref "C128") (pin "2") (pinfunction "2_2") (pintype "passive"))
      (node (ref "C129") (pin "2") (pinfunction "2_2") (pintype "passive"))
      (node (ref "C130") (pin "2") (pinfunction "2_2") (pintype "passive"))
      (node (ref "C131") (pin "2") (pinfunction "2_2") (pintype "passive"))
      (node (ref "C132") (pin "2") (pinfunction "2_2") (pintype "passive"))
      (node (ref "C133") (pin "2") (pinfunction "2_2") (pintype "passive"))
      (node (ref "C134") (pin "2") (pinfunction "2_2") (pintype "passive"))
      (node (ref "C135") (pin "2") (pinfunction "2_2") (pintype "passive"))
      (node (ref "C136") (pin "2") (pinfunction "2_2") (pintype "passive"))
      (node (ref "C137") (pin "2") (pinfunction "2_2") (pintype "passive"))
      (node (ref "C138") (pin "2") (pinfunction "2_2") (pintype "passive"))
      (node (ref "C139") (pin "2") (pinfunction "2_2") (pintype "passive"))
      (node (ref "C140") (pin "2") (pinfunction "2_2") (pintype "passive"))
      (node (ref "C141") (pin "2") (pinfunction "2_2") (pintype "passive"))
      (node (ref "C142") (pin "2") (pinfunction "2_2") (pintype "passive"))
      (node (ref "C143") (pin "2") (pinfunction "2_2") (pintype "passive"))
      (node (ref "C144") (pin "2") (pinfunction "2_2") (pintype "passive"))
      (node (ref "C145") (pin "2") (pinfunction "2_2") (pintype "passive"))
      (node (ref "C146") (pin "2") (pinfunction "2_2") (pintype "passive"))
      (node (ref "C147") (pin "2") (pinfunction "2_2") (pintype "passive"))
      (node (ref "C148") (pin "2") (pinfunction "2_2") (pintype "passive"))
      (node (ref "C149") (pin "2") (pinfunction "2_2") (pintype "passive"))
      (node (ref "C150") (pin "2") (pinfunction "2_2") (pintype "passive"))
      (node (ref "C151") (pin "2") (pinfunction "2_2") (pintype "passive"))
      (node (ref "C152") (pin "2") (pinfunction "2_2") (pintype "passive"))
      (node (ref "C153") (pin "2") (pinfunction "2_2") (pintype "passive"))
      (node (ref "C154") (pin "2") (pinfunction "2_2") (pintype "passive"))
      (node (ref "C155") (pin "2") (pinfunction "2_2") (pintype "passive"))
      (node (ref "C156") (pin "2") (pinfunction "2_2") (pintype "passive"))
      (node (ref "C157") (pin "2") (pinfunction "2_2") (pintype "passive"))
      (node (ref "C158") (pin "2") (pinfunction "2_2") (pintype "passive"))
      (node (ref "C159") (pin "2") (pinfunction "2_2") (pintype "passive"))
      (node (ref "C160") (pin "2") (pinfunction "2_2") (pintype "passive"))
      (node (ref "C161") (pin "2") (pinfunction "2_2") (pintype "passive"))
      (node (ref "C162") (pin "2") (pinfunction "2_2") (pintype "passive"))
      (node (ref "C163") (pin "2") (pinfunction "2_2") (pintype "passive"))
      (node (ref "C164") (pin "2") (pinfunction "2_2") (pintype "passive"))
      (node (ref "C165") (pin "2") (pinfunction "2_2") (pintype "passive"))
      (node (ref "C166") (pin "2") (pinfunction "2_2") (pintype "passive"))
      (node (ref "C167") (pin "2") (pinfunction "2_2") (pintype "passive"))
      (node (ref "C168") (pin "2") (pinfunction "2_2") (pintype "passive"))
      (node (ref "C169") (pin "2") (pinfunction "2_2") (pintype "passive"))
      (node (ref "C170") (pin "2") (pinfunction "2_2") (pintype "passive"))
      (node (ref "C171") (pin "2") (pinfunction "2_2") (pintype "passive"))
      (node (ref "C172") (pin "2") (pinfunction "2_2") (pintype "passive"))
      (node (ref "C173") (pin "2") (pinfunction "2_2") (pintype "passive"))
      (node (ref "C174") (pin "2") (pinfunction "2_2") (pintype "passive"))
      (node (ref "C175") (pin "2") (pinfunction "2_2") (pintype "passive"))
      (node (ref "C176") (pin "2") (pinfunction "2_2") (pintype "passive"))
      (node (ref "C177") (pin "2") (pinfunction "2_2") (pintype "passive"))
      (node (ref "C178") (pin "2") (pinfunction "2_2") (pintype "passive"))
      (node (ref "C179") (pin "2") (pinfunction "2_2") (pintype "passive"))
      (node (ref "C180") (pin "2") (pinfunction "2_2") (pintype "passive"))
      (node (ref "C181") (pin "2") (pinfunction "2_2") (pintype "passive"))
      (node (ref "C182") (pin "2") (pinfunction "2_2") (pintype "passive"))
      (node (ref "C183") (pin "2") (pinfunction "2_2") (pintype "passive"))
      (node (ref "C184") (pin "2") (pinfunction "2_2") (pintype "passive"))
      (node (ref "C185") (pin "2") (pinfunction "2_2") (pintype "passive"))
      (node (ref "C186") (pin "2") (pinfunction "2_2") (pintype "passive"))
      (node (ref "C187") (pin "2") (pinfunction "2_2") (pintype "passive"))
      (node (ref "C188") (pin "2") (pinfunction "2_2") (pintype "passive"))
      (node (ref "C189") (pin "2") (pinfunction "2_2") (pintype "passive"))
      (node (ref "C190") (pin "2") (pinfunction "2_2") (pintype "passive"))
      (node (ref "R51") (pin "2") (pinfunction "2_2") (pintype "passive"))
      (node (ref "R52") (pin "2") (pinfunction "2_2") (pintype "passive"))
      (node (ref "U7") (pin "13") (pinfunction "Vcc3_13") (pintype "power_in"))
      (node (ref "U7") (pin "18") (pinfunction "Vcc4_18") (pintype "power_in"))
      (node (ref "U7") (pin "19") (pinfunction "Vcc5_19") (pintype "power_in"))
      (node (ref "U7") (pin "22") (pinfunction "Vcc6_22") (pintype "power_in"))
      (node (ref "U7") (pin "24") (pinfunction "Vcc7_24") (pintype "power_in"))
      (node (ref "U7") (pin "3") (pinfunction "Vcc1_3") (pintype "power_in"))
      (node (ref "U7") (pin "30") (pinfunction "Vcc8_30") (pintype "power_in"))
      (node (ref "U7") (pin "31") (pinfunction "Vcc9_31") (pintype "power_in"))
      (node (ref "U7") (pin "33") (pinfunction "Vcc10_33") (pintype "power_in"))
      (node (ref "U7") (pin "37") (pinfunction "Vcc11_37") (pintype "power_in"))
      (node (ref "U7") (pin "40") (pinfunction "Vcc12_40") (pintype "power_in"))
      (node (ref "U7") (pin "43") (pinfunction "Vcc13_43") (pintype "power_in"))
      (node (ref "U7") (pin "46") (pinfunction "Vcc14_46") (pintype "power_in"))
      (node (ref "U7") (pin "8") (pinfunction "Vcc2_(VCO)_8") (pintype "power_in"))
    )
    (net (code "36") (name "unconnected-(U7-CLKin0_N-Pad21)") (class "Default")
      (node (ref "U7") (pin "21") (pinfunction "CLKin0_N_21") (pintype "passive+no_connect"))
    )
    (net (code "37") (name "unconnected-(U7-CLKin0_P-Pad20)") (class "Default")
      (node (ref "U7") (pin "20") (pinfunction "CLKin0_P_20") (pintype "passive+no_connect"))
    )
    (net (code "38") (name "unconnected-(U7-CLKin1_N-Pad26)") (class "Default")
      (node (ref "U7") (pin "26") (pinfunction "CLKin1_N_26") (pintype "passive+no_connect"))
    )
    (net (code "39") (name "unconnected-(U7-CLKin1_P-Pad25)") (class "Default")
      (node (ref "U7") (pin "25") (pinfunction "CLKin1_P_25") (pintype "passive+no_connect"))
    )
    (net (code "40") (name "unconnected-(U7-CLKout0_P-Pad14)") (class "Default")
      (node (ref "U7") (pin "14") (pinfunction "CLKout0_P_14") (pintype "passive"))
    )
    (net (code "41") (name "unconnected-(U7-CLKout2_N-Pad42)") (class "Default")
      (node (ref "U7") (pin "42") (pinfunction "CLKout2_N_42") (pintype "passive+no_connect"))
    )
    (net (code "42") (name "unconnected-(U7-CLKout2_P-Pad41)") (class "Default")
      (node (ref "U7") (pin "41") (pinfunction "CLKout2_P_41") (pintype "passive+no_connect"))
    )
    (net (code "43") (name "unconnected-(U7-CLKout4_N-Pad48)") (class "Default")
      (node (ref "U7") (pin "48") (pinfunction "CLKout4_N_48") (pintype "passive"))
    )
    (net (code "44") (name "unconnected-(U7-CLKout4_P-Pad47)") (class "Default")
      (node (ref "U7") (pin "47") (pinfunction "CLKout4_P_47") (pintype "passive"))
    )
    (net (code "45") (name "unconnected-(U7-CPout1-Pad23)") (class "Default")
      (node (ref "U7") (pin "23") (pinfunction "CPout1_23") (pintype "passive+no_connect"))
    )
    (net (code "46") (name "unconnected-(U7-Fout-Pad2)") (class "Default")
      (node (ref "U7") (pin "2") (pinfunction "Fout_2") (pintype "passive+no_connect"))
    )
    (net (code "47") (name "unconnected-(U7-NC-Pad7)") (class "Default")
      (node (ref "U7") (pin "7") (pinfunction "NC_7") (pintype "passive+no_connect"))
    )
    (net (code "48") (name "unconnected-(U7-SYNC#-Pad27)") (class "Default")
      (node (ref "U7") (pin "27") (pinfunction "SYNC#_27") (pintype "input+no_connect"))
    )
    (net (code "49") (name "unconnected-(U7-nCLKout0_N-Pad15)") (class "Default")
      (node (ref "U7") (pin "15") (pinfunction "nCLKout0_N_15") (pintype "passive"))
    )
  )
)
